# PowerCircuit_24V.net
KiCad netlist of a schematic drawn in Altium Designer
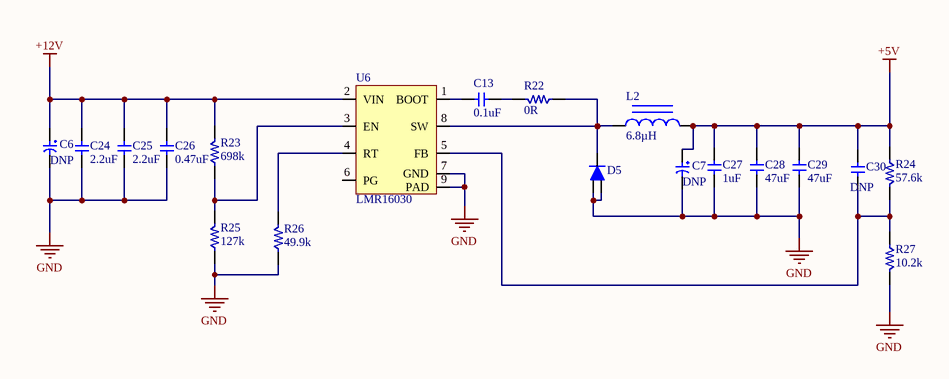
[diagram p0: PowerCircuit_24V.SchDoc]

(export (version "E")
  (design (tool "Eeschema 10.0.6"))
  (components
    (comp (ref "C6")
      (value "DNP")
      (footprint "Cap 6.3mm dia 5.4mm Height")
      (description "Polorised capacitor 47uF, 25V")
      (fields (field (name "Comment") "47uF, 25V"))
      (libsource (lib "PowerCircuit") (part "865080443007"))
    )
    (comp (ref "C7")
      (value "DNP")
      (footprint "Cap 6.3mm dia 5.4mm Height")
      (description "Polorised capacitor 47uF, 25V")
      (fields (field (name "Comment") "47uF, 25V"))
      (libsource (lib "PowerCircuit") (part "865080443007"))
    )
    (comp (ref "C13")
      (value "0.1uF")
      (footprint "0603")
      (description "Generic capacitor")
      (fields (field (name "Comment") "Generic Capacitor"))
      (libsource (lib "PowerCircuit") (part "Capacitor"))
    )
    (comp (ref "C24")
      (value "2.2uF")
      (footprint "Cap 1210")
      (description "Generic capacitor")
      (fields (field (name "Comment") "Generic Capacitor"))
      (libsource (lib "PowerCircuit") (part "Capacitor"))
    )
    (comp (ref "C25")
      (value "2.2uF")
      (footprint "Cap 1210")
      (description "Generic capacitor")
      (fields (field (name "Comment") "Generic Capacitor"))
      (libsource (lib "PowerCircuit") (part "Capacitor"))
    )
    (comp (ref "C26")
      (value "0.47uF")
      (footprint "0805")
      (description "Generic capacitor")
      (fields (field (name "Comment") "Generic Capacitor"))
      (libsource (lib "PowerCircuit") (part "Capacitor"))
    )
    (comp (ref "C27")
      (value "1uF")
      (footprint "0805")
      (description "Generic capacitor")
      (fields (field (name "Comment") "Generic Capacitor"))
      (libsource (lib "PowerCircuit") (part "Capacitor"))
    )
    (comp (ref "C28")
      (value "47uF")
      (footprint "Cap 1210")
      (description "Generic capacitor")
      (fields (field (name "Comment") "Generic Capacitor"))
      (libsource (lib "PowerCircuit") (part "Capacitor"))
    )
    (comp (ref "C29")
      (value "47uF")
      (footprint "Cap 1210")
      (description "Generic capacitor")
      (fields (field (name "Comment") "Generic Capacitor"))
      (libsource (lib "PowerCircuit") (part "Capacitor"))
    )
    (comp (ref "C30")
      (value "Generic Capacitor")
      (footprint "0603")
      (description "Generic capacitor")
      (fields (field (name "DIGIKEY") "DNP"))
      (libsource (lib "PowerCircuit") (part "Capacitor"))
    )
    (comp (ref "D5")
      (value "DIODE SCHOTTKY 60V 5A")
      (footprint "TO277A")
      (description "DIODE SCHOTTKY 60V 5A TO277A")
      (fields
        (field (name "MANUFACTURER") "Vishay Semiconductor Diodes Division")
        (field (name "MANUFACTURER PART NUMBER") "SS5P6-M3/86A")
      )
      (libsource (lib "PowerCircuit") (part "SS5P6-M3/86A"))
    )
    (comp (ref "L2")
      (value "FIXED IND 6.8UH 5.2A")
      (footprint "7447714068")
      (description "FIXED IND 6.8UH 5.2A 22 MOHM SMD")
      (fields
        (field (name "MANUFACTURER") "Wurth Electronics Inc.")
        (field (name "MANUFACTURER PART NUMBER") "7447714068")
        (field (name "INDUCTANCE") "6.8µH")
      )
      (libsource (lib "PowerCircuit") (part "7447714068"))
    )
    (comp (ref "R22")
      (value "0R")
      (footprint "0603")
      (description "Generic Resistor")
      (fields (field (name "Comment") "Resistor"))
      (libsource (lib "PowerCircuit") (part "Resistor"))
    )
    (comp (ref "R23")
      (value "698k")
      (footprint "0603")
      (description "Generic Resistor")
      (fields (field (name "Comment") "Resistor"))
      (libsource (lib "PowerCircuit") (part "Resistor"))
    )
    (comp (ref "R24")
      (value "57.6k")
      (footprint "0603")
      (description "Generic Resistor")
      (fields (field (name "Comment") "Resistor"))
      (libsource (lib "PowerCircuit") (part "Resistor"))
    )
    (comp (ref "R25")
      (value "127k")
      (footprint "0603")
      (description "Generic Resistor")
      (fields (field (name "Comment") "Resistor"))
      (libsource (lib "PowerCircuit") (part "Resistor"))
    )
    (comp (ref "R26")
      (value "49.9k")
      (footprint "0603")
      (description "Generic Resistor")
      (fields (field (name "Comment") "Resistor"))
      (libsource (lib "PowerCircuit") (part "Resistor"))
    )
    (comp (ref "R27")
      (value "10.2k")
      (footprint "0603")
      (description "Generic Resistor")
      (fields (field (name "Comment") "Resistor"))
      (libsource (lib "PowerCircuit") (part "Resistor"))
    )
    (comp (ref "U6")
      (value "LMR16030")
      (footprint "LMR16030")
      (description "IC REG BUCK ADJ 3A 8SOPWRPD")
      (fields
        (field (name "MANUFACTURER") "Texas Instruments")
        (field (name "MANUFACTURER PART NUMBER") "LMR16030PDDA")
      )
      (libsource (lib "PowerCircuit") (part "LMR16030"))
    )
  )
  (nets
    (net (code "1") (name "+5V") (class "Default")
      (node (ref "C27") (pin "1") (pinfunction "1_1") (pintype "passive"))
      (node (ref "C28") (pin "1") (pinfunction "1_1") (pintype "passive"))
      (node (ref "C29") (pin "1") (pinfunction "1_1") (pintype "passive"))
      (node (ref "C30") (pin "1") (pinfunction "1_1") (pintype "passive"))
      (node (ref "C7") (pin "1") (pinfunction "1_1") (pintype "passive"))
      (node (ref "L2") (pin "0") (pinfunction "0_0") (pintype "passive"))
      (node (ref "R24") (pin "1") (pinfunction "1_1") (pintype "passive"))
    )
    (net (code "2") (name "+12V") (class "Default")
      (node (ref "C24") (pin "1") (pinfunction "1_1") (pintype "passive"))
      (node (ref "C25") (pin "1") (pinfunction "1_1") (pintype "passive"))
      (node (ref "C26") (pin "1") (pinfunction "1_1") (pintype "passive"))
      (node (ref "C6") (pin "1") (pinfunction "1_1") (pintype "passive"))
      (node (ref "R23") (pin "2") (pinfunction "2_2") (pintype "passive"))
      (node (ref "U6") (pin "2") (pinfunction "VIN_2") (pintype "passive"))
    )
    (net (code "3") (name "GND") (class "Default")
      (node (ref "C24") (pin "2") (pinfunction "2_2") (pintype "passive"))
      (node (ref "C25") (pin "2") (pinfunction "2_2") (pintype "passive"))
      (node (ref "C26") (pin "2") (pinfunction "2_2") (pintype "passive"))
      (node (ref "C27") (pin "2") (pinfunction "2_2") (pintype "passive"))
      (node (ref "C28") (pin "2") (pinfunction "2_2") (pintype "passive"))
      (node (ref "C29") (pin "2") (pinfunction "2_2") (pintype "passive"))
      (node (ref "C6") (pin "2") (pinfunction "2_2") (pintype "passive"))
      (node (ref "C7") (pin "2") (pinfunction "2_2") (pintype "passive"))
      (node (ref "D5") (pin "1") (pinfunction "1_1") (pintype "passive"))
      (node (ref "D5") (pin "2") (pinfunction "2_2") (pintype "passive"))
      (node (ref "R25") (pin "1") (pinfunction "1_1") (pintype "passive"))
      (node (ref "R26") (pin "1") (pinfunction "1_1") (pintype "passive"))
      (node (ref "R27") (pin "2") (pinfunction "2_2") (pintype "passive"))
      (node (ref "U6") (pin "7") (pinfunction "GND_7") (pintype "passive"))
      (node (ref "U6") (pin "9") (pinfunction "PAD_9") (pintype "passive"))
    )
    (net (code "4") (name "Net-(C13-Pad2)") (class "Default")
      (node (ref "C13") (pin "2") (pinfunction "2_2") (pintype "passive"))
      (node (ref "R22") (pin "2") (pinfunction "2_2") (pintype "passive"))
    )
    (net (code "5") (name "Net-(U6-BOOT)") (class "Default")
      (node (ref "C13") (pin "1") (pinfunction "1_1") (pintype "passive"))
      (node (ref "U6") (pin "1") (pinfunction "BOOT_1") (pintype "passive"))
    )
    (net (code "6") (name "Net-(U6-EN)") (class "Default")
      (node (ref "R23") (pin "1") (pinfunction "1_1") (pintype "passive"))
      (node (ref "R25") (pin "2") (pinfunction "2_2") (pintype "passive"))
      (node (ref "U6") (pin "3") (pinfunction "EN_3") (pintype "passive"))
    )
    (net (code "7") (name "Net-(U6-FB)") (class "Default")
      (node (ref "C30") (pin "2") (pinfunction "2_2") (pintype "passive"))
      (node (ref "R24") (pin "2") (pinfunction "2_2") (pintype "passive"))
      (node (ref "R27") (pin "1") (pinfunction "1_1") (pintype "passive"))
      (node (ref "U6") (pin "5") (pinfunction "FB_5") (pintype "passive"))
    )
    (net (code "8") (name "Net-(U6-RT)") (class "Default")
      (node (ref "R26") (pin "2") (pinfunction "2_2") (pintype "passive"))
      (node (ref "U6") (pin "4") (pinfunction "RT_4") (pintype "passive"))
    )
    (net (code "9") (name "Net-(U6-SW)") (class "Default")
      (node (ref "D5") (pin "3") (pinfunction "3_3") (pintype "passive"))
      (node (ref "L2") (pin "1") (pinfunction "1_1") (pintype "passive"))
      (node (ref "R22") (pin "1") (pinfunction "1_1") (pintype "passive"))
      (node (ref "U6") (pin "8") (pinfunction "SW_8") (pintype "passive"))
    )
    (net (code "10") (name "unconnected-(U6-PG-Pad6)") (class "Default")
      (node (ref "U6") (pin "6") (pinfunction "PG_6") (pintype "passive"))
    )
  )
)
